# Signal_generator.net
KiCad netlist of a schematic drawn in Altium Designer
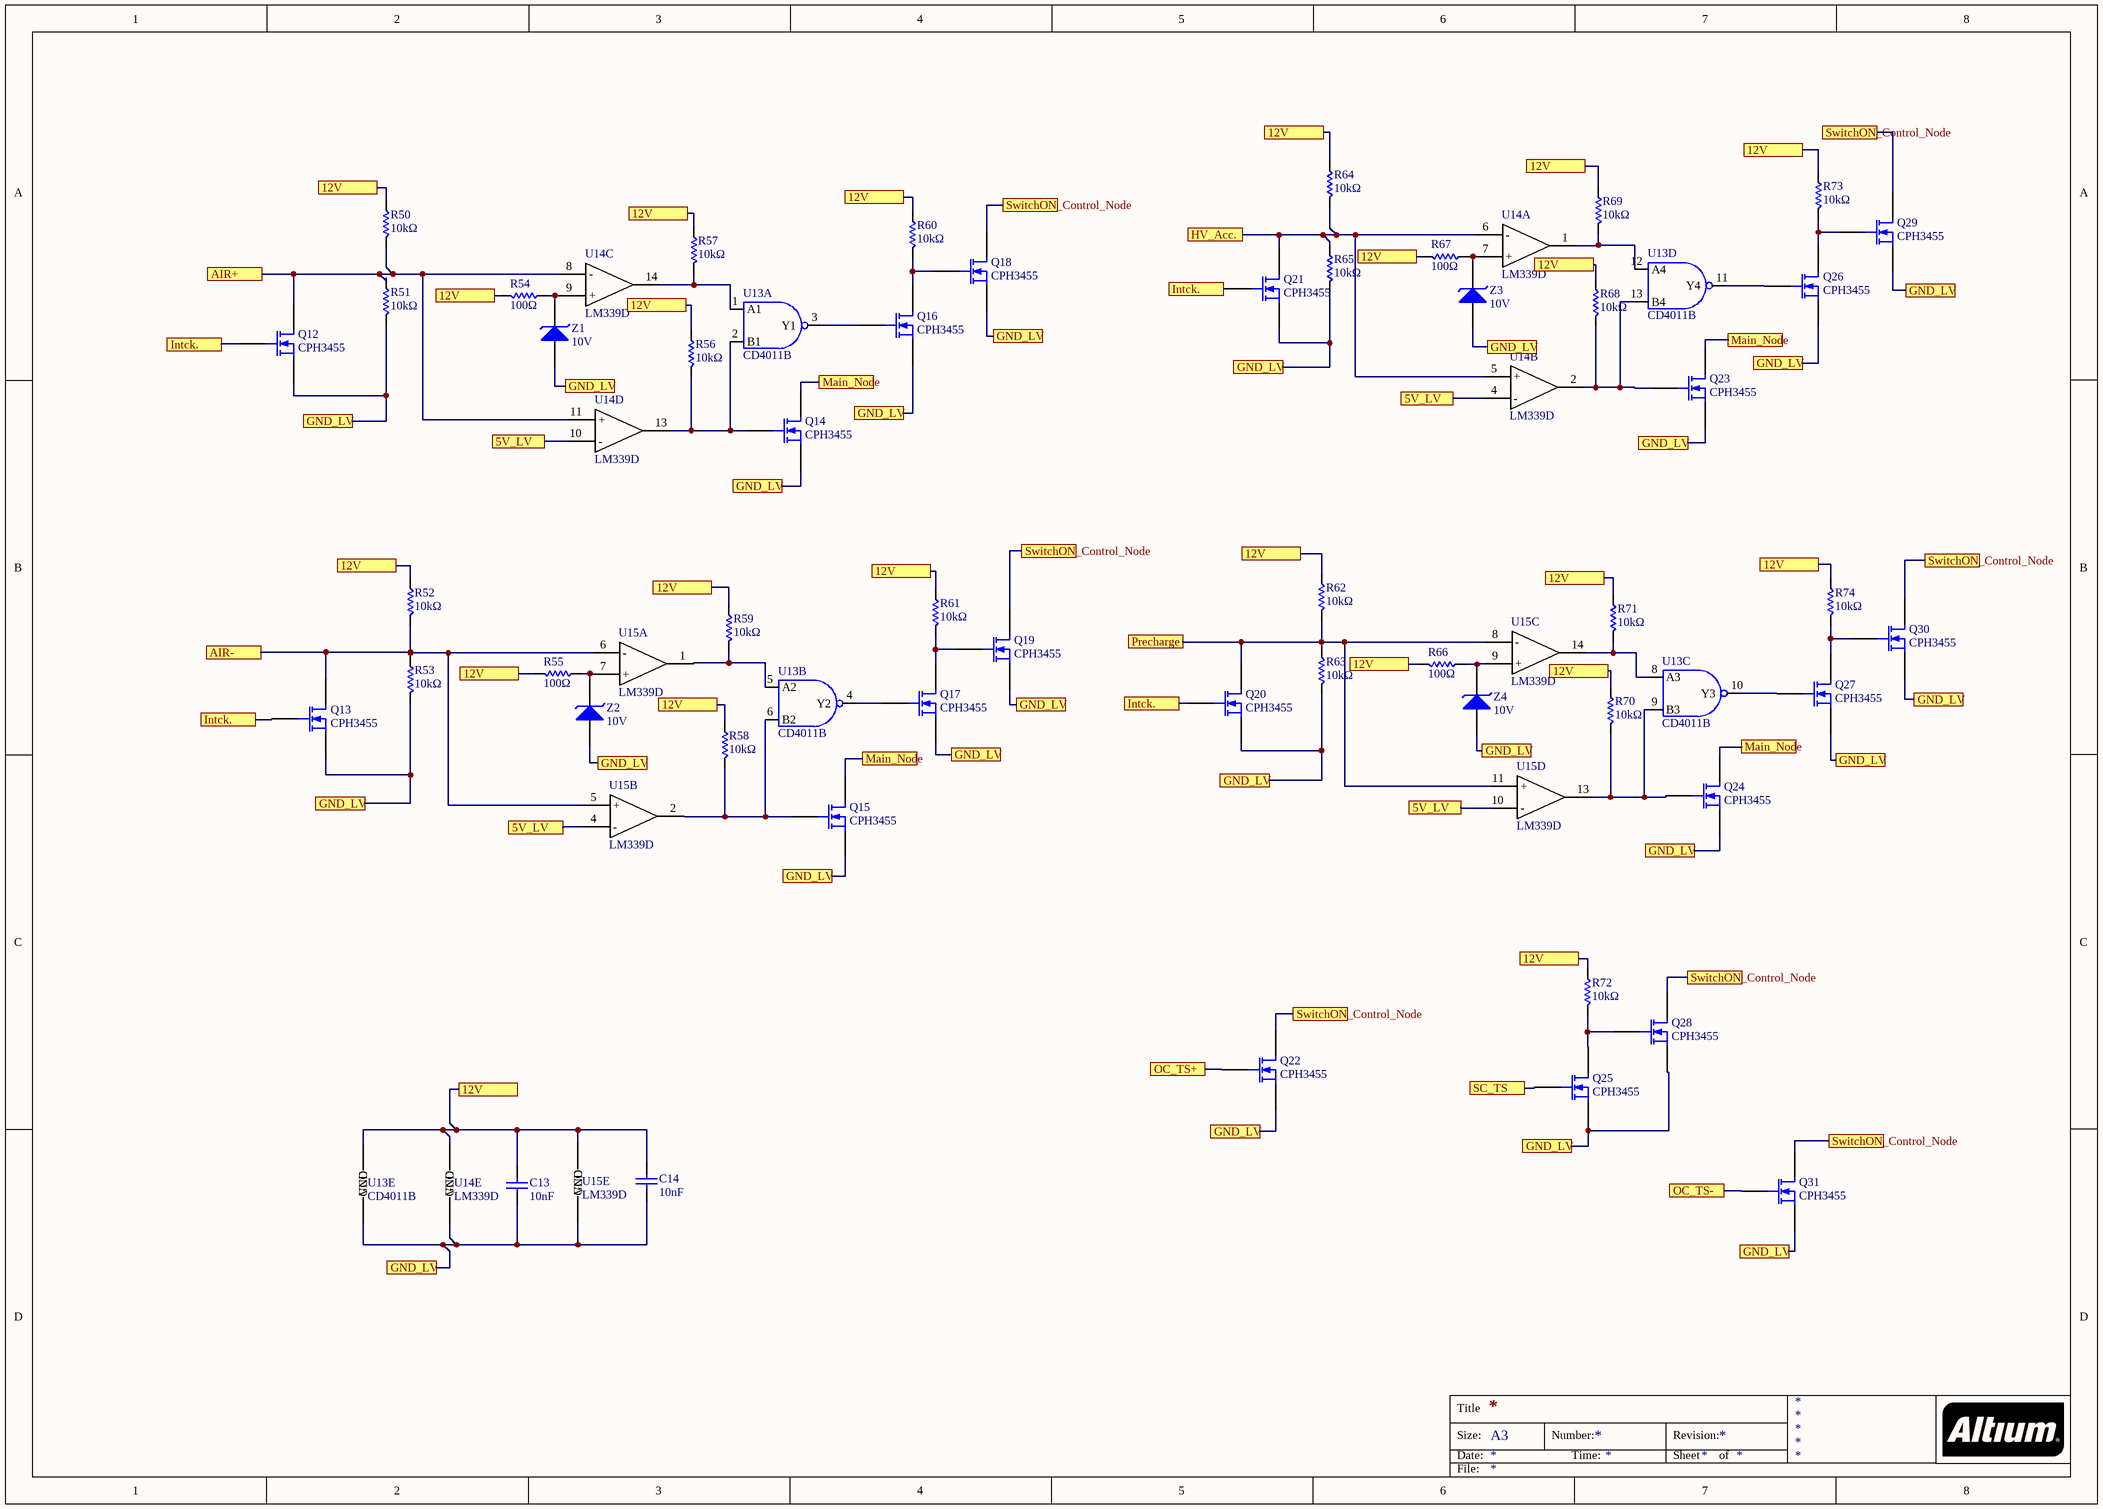
[diagram p0: Signal_generator.SchDoc]

(export (version "E")
  (design (tool "Eeschema 10.0.6"))
  (components
    (comp (ref "C13")
      (value "10nF")
      (footprint "0805_2x1.25x0.8mm_Reflow Soldering")
      (description "WCAP-CSGP Ceramic Capacitors, 0805, X7R, 50V, 10nF")
      (fields (field (name "PART NUMBER") "885012207092") (field (name "PUBLISHER") "Wurth Elektronik"))
      (libsource (lib "TSAL_Control") (part "885012207092"))
    )
    (comp (ref "C14")
      (value "10nF")
      (footprint "0805_2x1.25x0.8mm_Reflow Soldering")
      (description "WCAP-CSGP Ceramic Capacitors, 0805, X7R, 50V, 10nF")
      (fields (field (name "PART NUMBER") "885012207092") (field (name "PUBLISHER") "Wurth Elektronik"))
      (libsource (lib "TSAL_Control") (part "885012207092"))
    )
    (comp (ref "Q12")
      (value "CPH3455")
      (footprint "CPH3455")
      (description "Power MOSFET, 35V, 104 mohm, 3A, Single N-Channel")
      (fields (field (name "MANUFACTURER") "ON Semiconductor"))
      (libsource (lib "TSAL_Control") (part "CPH3455"))
    )
    (comp (ref "Q13")
      (value "CPH3455")
      (footprint "CPH3455")
      (description "Power MOSFET, 35V, 104 mohm, 3A, Single N-Channel")
      (fields (field (name "MANUFACTURER") "ON Semiconductor"))
      (libsource (lib "TSAL_Control") (part "CPH3455"))
    )
    (comp (ref "Q14")
      (value "CPH3455")
      (footprint "CPH3455")
      (description "Power MOSFET, 35V, 104 mohm, 3A, Single N-Channel")
      (fields (field (name "MANUFACTURER") "ON Semiconductor"))
      (libsource (lib "TSAL_Control") (part "CPH3455"))
    )
    (comp (ref "Q15")
      (value "CPH3455")
      (footprint "CPH3455")
      (description "Power MOSFET, 35V, 104 mohm, 3A, Single N-Channel")
      (fields (field (name "MANUFACTURER") "ON Semiconductor"))
      (libsource (lib "TSAL_Control") (part "CPH3455"))
    )
    (comp (ref "Q16")
      (value "CPH3455")
      (footprint "CPH3455")
      (description "Power MOSFET, 35V, 104 mohm, 3A, Single N-Channel")
      (fields (field (name "MANUFACTURER") "ON Semiconductor"))
      (libsource (lib "TSAL_Control") (part "CPH3455"))
    )
    (comp (ref "Q17")
      (value "CPH3455")
      (footprint "CPH3455")
      (description "Power MOSFET, 35V, 104 mohm, 3A, Single N-Channel")
      (fields (field (name "MANUFACTURER") "ON Semiconductor"))
      (libsource (lib "TSAL_Control") (part "CPH3455"))
    )
    (comp (ref "Q18")
      (value "CPH3455")
      (footprint "CPH3455")
      (description "Power MOSFET, 35V, 104 mohm, 3A, Single N-Channel")
      (fields (field (name "MANUFACTURER") "ON Semiconductor"))
      (libsource (lib "TSAL_Control") (part "CPH3455"))
    )
    (comp (ref "Q19")
      (value "CPH3455")
      (footprint "CPH3455")
      (description "Power MOSFET, 35V, 104 mohm, 3A, Single N-Channel")
      (fields (field (name "MANUFACTURER") "ON Semiconductor"))
      (libsource (lib "TSAL_Control") (part "CPH3455"))
    )
    (comp (ref "Q20")
      (value "CPH3455")
      (footprint "CPH3455")
      (description "Power MOSFET, 35V, 104 mohm, 3A, Single N-Channel")
      (fields (field (name "MANUFACTURER") "ON Semiconductor"))
      (libsource (lib "TSAL_Control") (part "CPH3455"))
    )
    (comp (ref "Q21")
      (value "CPH3455")
      (footprint "CPH3455")
      (description "Power MOSFET, 35V, 104 mohm, 3A, Single N-Channel")
      (fields (field (name "MANUFACTURER") "ON Semiconductor"))
      (libsource (lib "TSAL_Control") (part "CPH3455"))
    )
    (comp (ref "Q22")
      (value "CPH3455")
      (footprint "CPH3455")
      (description "Power MOSFET, 35V, 104 mohm, 3A, Single N-Channel")
      (fields (field (name "MANUFACTURER") "ON Semiconductor"))
      (libsource (lib "TSAL_Control") (part "CPH3455"))
    )
    (comp (ref "Q23")
      (value "CPH3455")
      (footprint "CPH3455")
      (description "Power MOSFET, 35V, 104 mohm, 3A, Single N-Channel")
      (fields (field (name "MANUFACTURER") "ON Semiconductor"))
      (libsource (lib "TSAL_Control") (part "CPH3455"))
    )
    (comp (ref "Q24")
      (value "CPH3455")
      (footprint "CPH3455")
      (description "Power MOSFET, 35V, 104 mohm, 3A, Single N-Channel")
      (fields (field (name "MANUFACTURER") "ON Semiconductor"))
      (libsource (lib "TSAL_Control") (part "CPH3455"))
    )
    (comp (ref "Q25")
      (value "CPH3455")
      (footprint "CPH3455")
      (description "Power MOSFET, 35V, 104 mohm, 3A, Single N-Channel")
      (fields (field (name "MANUFACTURER") "ON Semiconductor"))
      (libsource (lib "TSAL_Control") (part "CPH3455"))
    )
    (comp (ref "Q26")
      (value "CPH3455")
      (footprint "CPH3455")
      (description "Power MOSFET, 35V, 104 mohm, 3A, Single N-Channel")
      (fields (field (name "MANUFACTURER") "ON Semiconductor"))
      (libsource (lib "TSAL_Control") (part "CPH3455"))
    )
    (comp (ref "Q27")
      (value "CPH3455")
      (footprint "CPH3455")
      (description "Power MOSFET, 35V, 104 mohm, 3A, Single N-Channel")
      (fields (field (name "MANUFACTURER") "ON Semiconductor"))
      (libsource (lib "TSAL_Control") (part "CPH3455"))
    )
    (comp (ref "Q28")
      (value "CPH3455")
      (footprint "CPH3455")
      (description "Power MOSFET, 35V, 104 mohm, 3A, Single N-Channel")
      (fields (field (name "MANUFACTURER") "ON Semiconductor"))
      (libsource (lib "TSAL_Control") (part "CPH3455"))
    )
    (comp (ref "Q29")
      (value "CPH3455")
      (footprint "CPH3455")
      (description "Power MOSFET, 35V, 104 mohm, 3A, Single N-Channel")
      (fields (field (name "MANUFACTURER") "ON Semiconductor"))
      (libsource (lib "TSAL_Control") (part "CPH3455"))
    )
    (comp (ref "Q30")
      (value "CPH3455")
      (footprint "CPH3455")
      (description "Power MOSFET, 35V, 104 mohm, 3A, Single N-Channel")
      (fields (field (name "MANUFACTURER") "ON Semiconductor"))
      (libsource (lib "TSAL_Control") (part "CPH3455"))
    )
    (comp (ref "Q31")
      (value "CPH3455")
      (footprint "CPH3455")
      (description "Power MOSFET, 35V, 104 mohm, 3A, Single N-Channel")
      (fields (field (name "MANUFACTURER") "ON Semiconductor"))
      (libsource (lib "TSAL_Control") (part "CPH3455"))
    )
    (comp (ref "R50")
      (value "10kΩ")
      (footprint "CR0805")
      (description "Chip Resistor 0805")
      (fields (field (name "MANUFACTURER") "Bourns"))
      (libsource (lib "TSAL_Control") (part "CR0805-JW-103ELF"))
    )
    (comp (ref "R51")
      (value "10kΩ")
      (footprint "CR0805")
      (description "Chip Resistor 0805")
      (fields (field (name "MANUFACTURER") "Bourns"))
      (libsource (lib "TSAL_Control") (part "CR0805-JW-103ELF"))
    )
    (comp (ref "R52")
      (value "10kΩ")
      (footprint "CR0805")
      (description "Chip Resistor 0805")
      (fields (field (name "MANUFACTURER") "Bourns"))
      (libsource (lib "TSAL_Control") (part "CR0805-JW-103ELF"))
    )
    (comp (ref "R53")
      (value "10kΩ")
      (footprint "CR0805")
      (description "Chip Resistor 0805")
      (fields (field (name "MANUFACTURER") "Bourns"))
      (libsource (lib "TSAL_Control") (part "CR0805-JW-103ELF"))
    )
    (comp (ref "R54")
      (value "100Ω")
      (footprint "CR0805")
      (description "Chip Resistor 0805")
      (fields (field (name "MANUFACTURER") "Bourns"))
      (libsource (lib "TSAL_Control") (part "CR0805-FX-1000ELF"))
    )
    (comp (ref "R55")
      (value "100Ω")
      (footprint "CR0805")
      (description "Chip Resistor 0805")
      (fields (field (name "MANUFACTURER") "Bourns"))
      (libsource (lib "TSAL_Control") (part "CR0805-FX-1000ELF"))
    )
    (comp (ref "R56")
      (value "10kΩ")
      (footprint "CR0805")
      (description "Chip Resistor 0805")
      (fields (field (name "MANUFACTURER") "Bourns"))
      (libsource (lib "TSAL_Control") (part "CR0805-JW-103ELF"))
    )
    (comp (ref "R57")
      (value "10kΩ")
      (footprint "CR0805")
      (description "Chip Resistor 0805")
      (fields (field (name "MANUFACTURER") "Bourns"))
      (libsource (lib "TSAL_Control") (part "CR0805-JW-103ELF"))
    )
    (comp (ref "R58")
      (value "10kΩ")
      (footprint "CR0805")
      (description "Chip Resistor 0805")
      (fields (field (name "MANUFACTURER") "Bourns"))
      (libsource (lib "TSAL_Control") (part "CR0805-JW-103ELF"))
    )
    (comp (ref "R59")
      (value "10kΩ")
      (footprint "CR0805")
      (description "Chip Resistor 0805")
      (fields (field (name "MANUFACTURER") "Bourns"))
      (libsource (lib "TSAL_Control") (part "CR0805-JW-103ELF"))
    )
    (comp (ref "R60")
      (value "10kΩ")
      (footprint "CR0805")
      (description "Chip Resistor 0805")
      (fields (field (name "MANUFACTURER") "Bourns"))
      (libsource (lib "TSAL_Control") (part "CR0805-JW-103ELF"))
    )
    (comp (ref "R61")
      (value "10kΩ")
      (footprint "CR0805")
      (description "Chip Resistor 0805")
      (fields (field (name "MANUFACTURER") "Bourns"))
      (libsource (lib "TSAL_Control") (part "CR0805-JW-103ELF"))
    )
    (comp (ref "R62")
      (value "10kΩ")
      (footprint "CR0805")
      (description "Chip Resistor 0805")
      (fields (field (name "MANUFACTURER") "Bourns"))
      (libsource (lib "TSAL_Control") (part "CR0805-JW-103ELF"))
    )
    (comp (ref "R63")
      (value "10kΩ")
      (footprint "CR0805")
      (description "Chip Resistor 0805")
      (fields (field (name "MANUFACTURER") "Bourns"))
      (libsource (lib "TSAL_Control") (part "CR0805-JW-103ELF"))
    )
    (comp (ref "R64")
      (value "10kΩ")
      (footprint "CR0805")
      (description "Chip Resistor 0805")
      (fields (field (name "MANUFACTURER") "Bourns"))
      (libsource (lib "TSAL_Control") (part "CR0805-JW-103ELF"))
    )
    (comp (ref "R65")
      (value "10kΩ")
      (footprint "CR0805")
      (description "Chip Resistor 0805")
      (fields (field (name "MANUFACTURER") "Bourns"))
      (libsource (lib "TSAL_Control") (part "CR0805-JW-103ELF"))
    )
    (comp (ref "R66")
      (value "100Ω")
      (footprint "CR0805")
      (description "Chip Resistor 0805")
      (fields (field (name "MANUFACTURER") "Bourns"))
      (libsource (lib "TSAL_Control") (part "CR0805-FX-1000ELF"))
    )
    (comp (ref "R67")
      (value "100Ω")
      (footprint "CR0805")
      (description "Chip Resistor 0805")
      (fields (field (name "MANUFACTURER") "Bourns"))
      (libsource (lib "TSAL_Control") (part "CR0805-FX-1000ELF"))
    )
    (comp (ref "R68")
      (value "10kΩ")
      (footprint "CR0805")
      (description "Chip Resistor 0805")
      (fields (field (name "MANUFACTURER") "Bourns"))
      (libsource (lib "TSAL_Control") (part "CR0805-JW-103ELF"))
    )
    (comp (ref "R69")
      (value "10kΩ")
      (footprint "CR0805")
      (description "Chip Resistor 0805")
      (fields (field (name "MANUFACTURER") "Bourns"))
      (libsource (lib "TSAL_Control") (part "CR0805-JW-103ELF"))
    )
    (comp (ref "R70")
      (value "10kΩ")
      (footprint "CR0805")
      (description "Chip Resistor 0805")
      (fields (field (name "MANUFACTURER") "Bourns"))
      (libsource (lib "TSAL_Control") (part "CR0805-JW-103ELF"))
    )
    (comp (ref "R71")
      (value "10kΩ")
      (footprint "CR0805")
      (description "Chip Resistor 0805")
      (fields (field (name "MANUFACTURER") "Bourns"))
      (libsource (lib "TSAL_Control") (part "CR0805-JW-103ELF"))
    )
    (comp (ref "R72")
      (value "10kΩ")
      (footprint "CR0805")
      (description "Chip Resistor 0805")
      (fields (field (name "MANUFACTURER") "Bourns"))
      (libsource (lib "TSAL_Control") (part "CR0805-JW-103ELF"))
    )
    (comp (ref "R73")
      (value "10kΩ")
      (footprint "CR0805")
      (description "Chip Resistor 0805")
      (fields (field (name "MANUFACTURER") "Bourns"))
      (libsource (lib "TSAL_Control") (part "CR0805-JW-103ELF"))
    )
    (comp (ref "R74")
      (value "10kΩ")
      (footprint "CR0805")
      (description "Chip Resistor 0805")
      (fields (field (name "MANUFACTURER") "Bourns"))
      (libsource (lib "TSAL_Control") (part "CR0805-JW-103ELF"))
    )
    (comp (ref "U13")
      (value "CD4011B")
      (footprint "CD4011BM")
      (description "QUAD CMOS NAND GATES")
      (fields (field (name "MANUFACTURER") "Texas Instruments"))
      (libsource (lib "TSAL_Control") (part "CD4011B"))
    )
    (comp (ref "U14")
      (value "LM339D")
      (footprint "LM339D")
      (description "Quad Differential Comparators")
      (fields (field (name "MANUFACTURER") "Texas Intstruments"))
      (libsource (lib "TSAL_Control") (part "LM339D"))
    )
    (comp (ref "U15")
      (value "LM339D")
      (footprint "LM339D")
      (description "Quad Differential Comparators")
      (fields (field (name "MANUFACTURER") "Texas Intstruments"))
      (libsource (lib "TSAL_Control") (part "LM339D"))
    )
    (comp (ref "Z1")
      (value "10V")
      (footprint "MMSZ5240BT1G")
      (description "Zener Voltage Regulators")
      (fields (field (name "MANUFACTURER") "ON Semiconductor"))
      (libsource (lib "TSAL_Control") (part "MMSZ5240BT1G"))
    )
    (comp (ref "Z2")
      (value "10V")
      (footprint "MMSZ5240BT1G")
      (description "Zener Voltage Regulators")
      (fields (field (name "MANUFACTURER") "ON Semiconductor"))
      (libsource (lib "TSAL_Control") (part "MMSZ5240BT1G"))
    )
    (comp (ref "Z3")
      (value "10V")
      (footprint "MMSZ5240BT1G")
      (description "Zener Voltage Regulators")
      (fields (field (name "MANUFACTURER") "ON Semiconductor"))
      (libsource (lib "TSAL_Control") (part "MMSZ5240BT1G"))
    )
    (comp (ref "Z4")
      (value "10V")
      (footprint "MMSZ5240BT1G")
      (description "Zener Voltage Regulators")
      (fields (field (name "MANUFACTURER") "ON Semiconductor"))
      (libsource (lib "TSAL_Control") (part "MMSZ5240BT1G"))
    )
  )
  (nets
    (net (code "1") (name "/5V_LV") (class "Default")
      (node (ref "U14") (pin "10") (pinfunction "-_10") (pintype "passive"))
      (node (ref "U14") (pin "4") (pinfunction "-_4") (pintype "passive"))
      (node (ref "U15") (pin "10") (pinfunction "-_10") (pintype "passive"))
      (node (ref "U15") (pin "4") (pinfunction "-_4") (pintype "passive"))
    )
    (net (code "2") (name "/12V") (class "Default")
      (node (ref "C13") (pin "2") (pinfunction "2_2") (pintype "passive"))
      (node (ref "C14") (pin "2") (pinfunction "2_2") (pintype "passive"))
      (node (ref "R50") (pin "2") (pinfunction "2_2") (pintype "passive"))
      (node (ref "R52") (pin "2") (pinfunction "2_2") (pintype "passive"))
      (node (ref "R54") (pin "1") (pinfunction "1_1") (pintype "passive"))
      (node (ref "R55") (pin "1") (pinfunction "1_1") (pintype "passive"))
      (node (ref "R56") (pin "2") (pinfunction "2_2") (pintype "passive"))
      (node (ref "R57") (pin "2") (pinfunction "2_2") (pintype "passive"))
      (node (ref "R58") (pin "2") (pinfunction "2_2") (pintype "passive"))
      (node (ref "R59") (pin "2") (pinfunction "2_2") (pintype "passive"))
      (node (ref "R60") (pin "2") (pinfunction "2_2") (pintype "passive"))
      (node (ref "R61") (pin "2") (pinfunction "2_2") (pintype "passive"))
      (node (ref "R62") (pin "2") (pinfunction "2_2") (pintype "passive"))
      (node (ref "R64") (pin "2") (pinfunction "2_2") (pintype "passive"))
      (node (ref "R66") (pin "1") (pinfunction "1_1") (pintype "passive"))
      (node (ref "R67") (pin "1") (pinfunction "1_1") (pintype "passive"))
      (node (ref "R68") (pin "2") (pinfunction "2_2") (pintype "passive"))
      (node (ref "R69") (pin "2") (pinfunction "2_2") (pintype "passive"))
      (node (ref "R70") (pin "2") (pinfunction "2_2") (pintype "passive"))
      (node (ref "R71") (pin "2") (pinfunction "2_2") (pintype "passive"))
      (node (ref "R72") (pin "2") (pinfunction "2_2") (pintype "passive"))
      (node (ref "R73") (pin "2") (pinfunction "2_2") (pintype "passive"))
      (node (ref "R74") (pin "2") (pinfunction "2_2") (pintype "passive"))
      (node (ref "U13") (pin "14") (pinfunction "VCC_14") (pintype "power_in"))
      (node (ref "U14") (pin "3") (pinfunction "VCC_3") (pintype "power_in"))
      (node (ref "U15") (pin "3") (pinfunction "VCC_3") (pintype "power_in"))
    )
    (net (code "4") (name "/AIR+") (class "Default")
      (node (ref "Q12") (pin "2") (pinfunction "D_2") (pintype "passive"))
      (node (ref "R50") (pin "1") (pinfunction "1_1") (pintype "passive"))
      (node (ref "R51") (pin "2") (pinfunction "2_2") (pintype "passive"))
      (node (ref "U14") (pin "11") (pinfunction "+_11") (pintype "passive"))
      (node (ref "U14") (pin "8") (pinfunction "-_8") (pintype "passive"))
    )
    (net (code "5") (name "/AIR-") (class "Default")
      (node (ref "Q13") (pin "2") (pinfunction "D_2") (pintype "passive"))
      (node (ref "R52") (pin "1") (pinfunction "1_1") (pintype "passive"))
      (node (ref "R53") (pin "2") (pinfunction "2_2") (pintype "passive"))
      (node (ref "U15") (pin "5") (pinfunction "+_5") (pintype "passive"))
      (node (ref "U15") (pin "6") (pinfunction "-_6") (pintype "passive"))
    )
    (net (code "6") (name "/GND_LV") (class "Default")
      (node (ref "C13") (pin "1") (pinfunction "1_1") (pintype "passive"))
      (node (ref "C14") (pin "1") (pinfunction "1_1") (pintype "passive"))
      (node (ref "Q12") (pin "3") (pinfunction "S_3") (pintype "passive"))
      (node (ref "Q13") (pin "3") (pinfunction "S_3") (pintype "passive"))
      (node (ref "Q14") (pin "3") (pinfunction "S_3") (pintype "passive"))
      (node (ref "Q15") (pin "3") (pinfunction "S_3") (pintype "passive"))
      (node (ref "Q16") (pin "3") (pinfunction "S_3") (pintype "passive"))
      (node (ref "Q17") (pin "3") (pinfunction "S_3") (pintype "passive"))
      (node (ref "Q18") (pin "3") (pinfunction "S_3") (pintype "passive"))
      (node (ref "Q19") (pin "3") (pinfunction "S_3") (pintype "passive"))
      (node (ref "Q20") (pin "3") (pinfunction "S_3") (pintype "passive"))
      (node (ref "Q21") (pin "3") (pinfunction "S_3") (pintype "passive"))
      (node (ref "Q22") (pin "3") (pinfunction "S_3") (pintype "passive"))
      (node (ref "Q23") (pin "3") (pinfunction "S_3") (pintype "passive"))
      (node (ref "Q24") (pin "3") (pinfunction "S_3") (pintype "passive"))
      (node (ref "Q25") (pin "3") (pinfunction "S_3") (pintype "passive"))
      (node (ref "Q26") (pin "3") (pinfunction "S_3") (pintype "passive"))
      (node (ref "Q27") (pin "3") (pinfunction "S_3") (pintype "passive"))
      (node (ref "Q28") (pin "3") (pinfunction "S_3") (pintype "passive"))
      (node (ref "Q29") (pin "3") (pinfunction "S_3") (pintype "passive"))
      (node (ref "Q30") (pin "3") (pinfunction "S_3") (pintype "passive"))
      (node (ref "Q31") (pin "3") (pinfunction "S_3") (pintype "passive"))
      (node (ref "R51") (pin "1") (pinfunction "1_1") (pintype "passive"))
      (node (ref "R53") (pin "1") (pinfunction "1_1") (pintype "passive"))
      (node (ref "R63") (pin "1") (pinfunction "1_1") (pintype "passive"))
      (node (ref "R65") (pin "1") (pinfunction "1_1") (pintype "passive"))
      (node (ref "U13") (pin "7") (pinfunction "GND_7") (pintype "power_in"))
      (node (ref "U14") (pin "12") (pinfunction "GND_12") (pintype "power_in"))
      (node (ref "U15") (pin "12") (pinfunction "GND_12") (pintype "power_in"))
      (node (ref "Z1") (pin "2") (pinfunction "A_2") (pintype "passive"))
      (node (ref "Z2") (pin "2") (pinfunction "A_2") (pintype "passive"))
      (node (ref "Z3") (pin "2") (pinfunction "A_2") (pintype "passive"))
      (node (ref "Z4") (pin "2") (pinfunction "A_2") (pintype "passive"))
    )
    (net (code "7") (name "/HV_Acc.") (class "Default")
      (node (ref "Q21") (pin "2") (pinfunction "D_2") (pintype "passive"))
      (node (ref "R64") (pin "1") (pinfunction "1_1") (pintype "passive"))
      (node (ref "R65") (pin "2") (pinfunction "2_2") (pintype "passive"))
      (node (ref "U14") (pin "5") (pinfunction "+_5") (pintype "passive"))
      (node (ref "U14") (pin "6") (pinfunction "-_6") (pintype "passive"))
    )
    (net (code "8") (name "/Intck.") (class "Default")
      (node (ref "Q12") (pin "1") (pinfunction "G_1") (pintype "passive"))
      (node (ref "Q13") (pin "1") (pinfunction "G_1") (pintype "passive"))
      (node (ref "Q20") (pin "1") (pinfunction "G_1") (pintype "passive"))
      (node (ref "Q21") (pin "1") (pinfunction "G_1") (pintype "passive"))
    )
    (net (code "9") (name "/Main_Node") (class "Default")
      (node (ref "Q14") (pin "2") (pinfunction "D_2") (pintype "passive"))
      (node (ref "Q15") (pin "2") (pinfunction "D_2") (pintype "passive"))
      (node (ref "Q23") (pin "2") (pinfunction "D_2") (pintype "passive"))
      (node (ref "Q24") (pin "2") (pinfunction "D_2") (pintype "passive"))
    )
    (net (code "10") (name "/OC_TS+") (class "Default")
      (node (ref "Q22") (pin "1") (pinfunction "G_1") (pintype "passive"))
    )
    (net (code "11") (name "/OC_TS-") (class "Default")
      (node (ref "Q31") (pin "1") (pinfunction "G_1") (pintype "passive"))
    )
    (net (code "12") (name "/Precharge") (class "Default")
      (node (ref "Q20") (pin "2") (pinfunction "D_2") (pintype "passive"))
      (node (ref "R62") (pin "1") (pinfunction "1_1") (pintype "passive"))
      (node (ref "R63") (pin "2") (pinfunction "2_2") (pintype "passive"))
      (node (ref "U15") (pin "11") (pinfunction "+_11") (pintype "passive"))
      (node (ref "U15") (pin "8") (pinfunction "-_8") (pintype "passive"))
    )
    (net (code "13") (name "/SC_TS") (class "Default")
      (node (ref "Q25") (pin "1") (pinfunction "G_1") (pintype "passive"))
    )
    (net (code "14") (name "/SwitchON_Control_Node") (class "Default")
      (node (ref "Q18") (pin "2") (pinfunction "D_2") (pintype "passive"))
      (node (ref "Q19") (pin "2") (pinfunction "D_2") (pintype "passive"))
      (node (ref "Q22") (pin "2") (pinfunction "D_2") (pintype "passive"))
      (node (ref "Q28") (pin "2") (pinfunction "D_2") (pintype "passive"))
      (node (ref "Q29") (pin "2") (pinfunction "D_2") (pintype "passive"))
      (node (ref "Q30") (pin "2") (pinfunction "D_2") (pintype "passive"))
      (node (ref "Q31") (pin "2") (pinfunction "D_2") (pintype "passive"))
    )
    (net (code "15") (name "Net-(Q14-G)") (class "Default")
      (node (ref "Q14") (pin "1") (pinfunction "G_1") (pintype "passive"))
      (node (ref "R56") (pin "1") (pinfunction "1_1") (pintype "passive"))
      (node (ref "U13") (pin "2") (pinfunction "B1_2") (pintype "passive"))
      (node (ref "U14") (pin "13") (pinfunction "4OUT_13") (pintype "passive"))
    )
    (net (code "16") (name "Net-(Q15-G)") (class "Default")
      (node (ref "Q15") (pin "1") (pinfunction "G_1") (pintype "passive"))
      (node (ref "R58") (pin "1") (pinfunction "1_1") (pintype "passive"))
      (node (ref "U13") (pin "6") (pinfunction "B2_6") (pintype "passive"))
      (node (ref "U15") (pin "2") (pinfunction "2OUT_2") (pintype "passive"))
    )
    (net (code "17") (name "Net-(Q16-D)") (class "Default")
      (node (ref "Q16") (pin "2") (pinfunction "D_2") (pintype "passive"))
      (node (ref "Q18") (pin "1") (pinfunction "G_1") (pintype "passive"))
      (node (ref "R60") (pin "1") (pinfunction "1_1") (pintype "passive"))
    )
    (net (code "18") (name "Net-(Q16-G)") (class "Default")
      (node (ref "Q16") (pin "1") (pinfunction "G_1") (pintype "passive"))
      (node (ref "U13") (pin "3") (pinfunction "Y1_3") (pintype "passive"))
    )
    (net (code "19") (name "Net-(Q17-D)") (class "Default")
      (node (ref "Q17") (pin "2") (pinfunction "D_2") (pintype "passive"))
      (node (ref "Q19") (pin "1") (pinfunction "G_1") (pintype "passive"))
      (node (ref "R61") (pin "1") (pinfunction "1_1") (pintype "passive"))
    )
    (net (code "20") (name "Net-(Q17-G)") (class "Default")
      (node (ref "Q17") (pin "1") (pinfunction "G_1") (pintype "passive"))
      (node (ref "U13") (pin "4") (pinfunction "Y2_4") (pintype "passive"))
    )
    (net (code "21") (name "Net-(Q23-G)") (class "Default")
      (node (ref "Q23") (pin "1") (pinfunction "G_1") (pintype "passive"))
      (node (ref "R68") (pin "1") (pinfunction "1_1") (pintype "passive"))
      (node (ref "U13") (pin "13") (pinfunction "B4_13") (pintype "passive"))
      (node (ref "U14") (pin "2") (pinfunction "2OUT_2") (pintype "passive"))
    )
    (net (code "22") (name "Net-(Q24-G)") (class "Default")
      (node (ref "Q24") (pin "1") (pinfunction "G_1") (pintype "passive"))
      (node (ref "R70") (pin "1") (pinfunction "1_1") (pintype "passive"))
      (node (ref "U13") (pin "9") (pinfunction "B3_9") (pintype "passive"))
      (node (ref "U15") (pin "13") (pinfunction "4OUT_13") (pintype "passive"))
    )
    (net (code "23") (name "Net-(Q25-D)") (class "Default")
      (node (ref "Q25") (pin "2") (pinfunction "D_2") (pintype "passive"))
      (node (ref "Q28") (pin "1") (pinfunction "G_1") (pintype "passive"))
      (node (ref "R72") (pin "1") (pinfunction "1_1") (pintype "passive"))
    )
    (net (code "24") (name "Net-(Q26-D)") (class "Default")
      (node (ref "Q26") (pin "2") (pinfunction "D_2") (pintype "passive"))
      (node (ref "Q29") (pin "1") (pinfunction "G_1") (pintype "passive"))
      (node (ref "R73") (pin "1") (pinfunction "1_1") (pintype "passive"))
    )
    (net (code "25") (name "Net-(Q26-G)") (class "Default")
      (node (ref "Q26") (pin "1") (pinfunction "G_1") (pintype "passive"))
      (node (ref "U13") (pin "11") (pinfunction "Y4_11") (pintype "passive"))
    )
    (net (code "26") (name "Net-(Q27-D)") (class "Default")
      (node (ref "Q27") (pin "2") (pinfunction "D_2") (pintype "passive"))
      (node (ref "Q30") (pin "1") (pinfunction "G_1") (pintype "passive"))
      (node (ref "R74") (pin "1") (pinfunction "1_1") (pintype "passive"))
    )
    (net (code "27") (name "Net-(Q27-G)") (class "Default")
      (node (ref "Q27") (pin "1") (pinfunction "G_1") (pintype "passive"))
      (node (ref "U13") (pin "10") (pinfunction "Y3_10") (pintype "passive"))
    )
    (net (code "28") (name "Net-(U13A-A1)") (class "Default")
      (node (ref "R57") (pin "1") (pinfunction "1_1") (pintype "passive"))
      (node (ref "U13") (pin "1") (pinfunction "A1_1") (pintype "passive"))
      (node (ref "U14") (pin "14") (pinfunction "3OUT_14") (pintype "passive"))
    )
    (net (code "29") (name "Net-(U13B-A2)") (class "Default")
      (node (ref "R59") (pin "1") (pinfunction "1_1") (pintype "passive"))
      (node (ref "U13") (pin "5") (pinfunction "A2_5") (pintype "passive"))
      (node (ref "U15") (pin "1") (pinfunction "1OUT_1") (pintype "passive"))
    )
    (net (code "30") (name "Net-(U13C-A3)") (class "Default")
      (node (ref "R71") (pin "1") (pinfunction "1_1") (pintype "passive"))
      (node (ref "U13") (pin "8") (pinfunction "A3_8") (pintype "passive"))
      (node (ref "U15") (pin "14") (pinfunction "3OUT_14") (pintype "passive"))
    )
    (net (code "31") (name "Net-(U13D-A4)") (class "Default")
      (node (ref "R69") (pin "1") (pinfunction "1_1") (pintype "passive"))
      (node (ref "U13") (pin "12") (pinfunction "A4_12") (pintype "passive"))
      (node (ref "U14") (pin "1") (pinfunction "1OUT_1") (pintype "passive"))
    )
    (net (code "32") (name "Net-(U14A-+)") (class "Default")
      (node (ref "R67") (pin "2") (pinfunction "2_2") (pintype "passive"))
      (node (ref "U14") (pin "7") (pinfunction "+_7") (pintype "passive"))
      (node (ref "Z3") (pin "1") (pinfunction "K_1") (pintype "passive"))
    )
    (net (code "33") (name "Net-(U14C-+)") (class "Default")
      (node (ref "R54") (pin "2") (pinfunction "2_2") (pintype "passive"))
      (node (ref "U14") (pin "9") (pinfunction "+_9") (pintype "passive"))
      (node (ref "Z1") (pin "1") (pinfunction "K_1") (pintype "passive"))
    )
    (net (code "34") (name "Net-(U15A-+)") (class "Default")
      (node (ref "R55") (pin "2") (pinfunction "2_2") (pintype "passive"))
      (node (ref "U15") (pin "7") (pinfunction "+_7") (pintype "passive"))
      (node (ref "Z2") (pin "1") (pinfunction "K_1") (pintype "passive"))
    )
    (net (code "35") (name "Net-(U15C-+)") (class "Default")
      (node (ref "R66") (pin "2") (pinfunction "2_2") (pintype "passive"))
      (node (ref "U15") (pin "9") (pinfunction "+_9") (pintype "passive"))
      (node (ref "Z4") (pin "1") (pinfunction "K_1") (pintype "passive"))
    )
  )
)
